# Overdrive.net
KiCad netlist of a schematic drawn in EAGLE
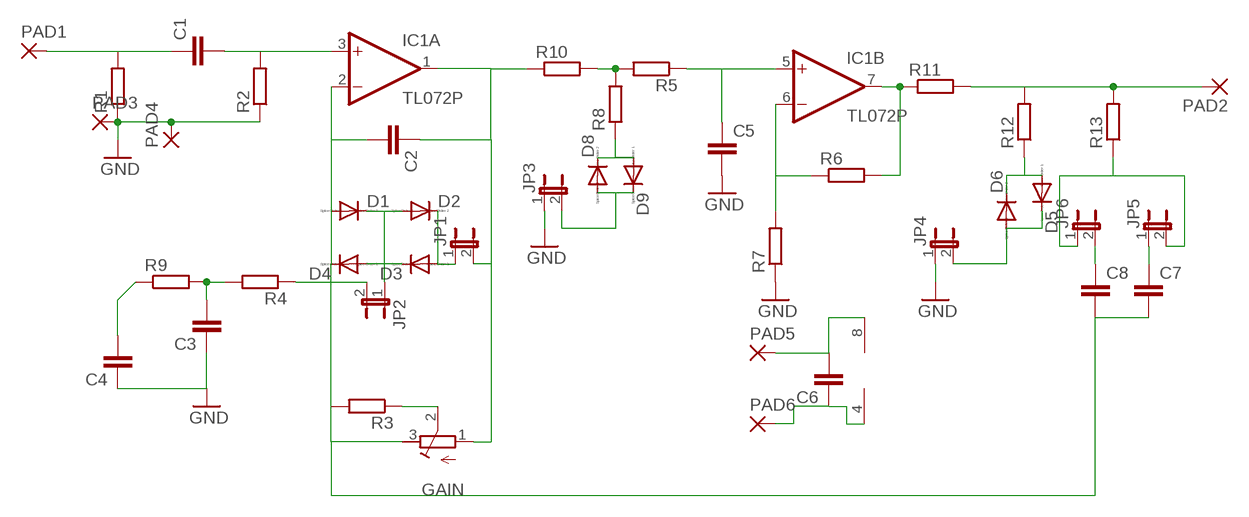
[diagram p0: schematic, sheet 1]

(export (version "E")
  (design (tool "Eeschema 10.0.6"))
  (components
    (comp (ref "C1")
      (value "C-EU050-030X075")
      (footprint "eagle-import:C050-030X075")
      (libsource (lib "eagle-import") (part "C-EU050-030X075"))
    )
    (comp (ref "C2")
      (value "C-EU050-030X075")
      (footprint "eagle-import:C050-030X075")
      (libsource (lib "eagle-import") (part "C-EU050-030X075"))
    )
    (comp (ref "C3")
      (value "C-EU050-030X075")
      (footprint "eagle-import:C050-030X075")
      (libsource (lib "eagle-import") (part "C-EU050-030X075"))
    )
    (comp (ref "C4")
      (value "C-EU050-030X075")
      (footprint "eagle-import:C050-030X075")
      (libsource (lib "eagle-import") (part "C-EU050-030X075"))
    )
    (comp (ref "C5")
      (value "C-EU050-030X075")
      (footprint "eagle-import:C050-030X075")
      (libsource (lib "eagle-import") (part "C-EU050-030X075"))
    )
    (comp (ref "C6")
      (value "C-EU050-030X075")
      (footprint "eagle-import:C050-030X075")
      (libsource (lib "eagle-import") (part "C-EU050-030X075"))
    )
    (comp (ref "C7")
      (value "C-EU050-030X075")
      (footprint "eagle-import:C050-030X075")
      (libsource (lib "eagle-import") (part "C-EU050-030X075"))
    )
    (comp (ref "C8")
      (value "C-EU050-030X075")
      (footprint "eagle-import:C050-030X075")
      (libsource (lib "eagle-import") (part "C-EU050-030X075"))
    )
    (comp (ref "D1")
      (value "1N4148DO35-7")
      (footprint "eagle-import:DO35-7")
      (libsource (lib "eagle-import") (part "1N4148DO35-7"))
    )
    (comp (ref "D2")
      (value "1N4148DO35-7")
      (footprint "eagle-import:DO35-7")
      (libsource (lib "eagle-import") (part "1N4148DO35-7"))
    )
    (comp (ref "D3")
      (value "1N4148DO35-7")
      (footprint "eagle-import:DO35-7")
      (libsource (lib "eagle-import") (part "1N4148DO35-7"))
    )
    (comp (ref "D4")
      (value "1N4148DO35-7")
      (footprint "eagle-import:DO35-7")
      (libsource (lib "eagle-import") (part "1N4148DO35-7"))
    )
    (comp (ref "D5")
      (value "1N4148DO35-7")
      (footprint "eagle-import:DO35-7")
      (libsource (lib "eagle-import") (part "1N4148DO35-7"))
    )
    (comp (ref "D6")
      (value "1N4148DO35-7")
      (footprint "eagle-import:DO35-7")
      (libsource (lib "eagle-import") (part "1N4148DO35-7"))
    )
    (comp (ref "D8")
      (value "1N4148DO35-7")
      (footprint "eagle-import:DO35-7")
      (libsource (lib "eagle-import") (part "1N4148DO35-7"))
    )
    (comp (ref "D9")
      (value "1N4148DO35-7")
      (footprint "eagle-import:DO35-7")
      (libsource (lib "eagle-import") (part "1N4148DO35-7"))
    )
    (comp (ref "GAIN")
      (value "R-TRIMM64W")
      (footprint "eagle-import:RTRIM64W")
      (libsource (lib "eagle-import") (part "R-TRIMM64W"))
    )
    (comp (ref "IC1")
      (value "TL072P")
      (footprint "eagle-import:DIL08")
      (libsource (lib "eagle-import") (part "TL072P"))
    )
    (comp (ref "JP1")
      (value "JP1E")
      (footprint "eagle-import:JP1")
      (libsource (lib "eagle-import") (part "JP1E"))
    )
    (comp (ref "JP2")
      (value "JP1E")
      (footprint "eagle-import:JP1")
      (libsource (lib "eagle-import") (part "JP1E"))
    )
    (comp (ref "JP3")
      (value "JP1E")
      (footprint "eagle-import:JP1")
      (libsource (lib "eagle-import") (part "JP1E"))
    )
    (comp (ref "JP4")
      (value "JP1E")
      (footprint "eagle-import:JP1")
      (libsource (lib "eagle-import") (part "JP1E"))
    )
    (comp (ref "JP5")
      (value "JP1E")
      (footprint "eagle-import:JP1")
      (libsource (lib "eagle-import") (part "JP1E"))
    )
    (comp (ref "JP6")
      (value "JP1E")
      (footprint "eagle-import:JP1")
      (libsource (lib "eagle-import") (part "JP1E"))
    )
    (comp (ref "PAD1")
      (value "WIREPAD2,54/0,8")
      (footprint "eagle-import:2,54_0,8")
      (libsource (lib "eagle-import") (part "WIREPAD2,54/0,8"))
    )
    (comp (ref "PAD2")
      (value "WIREPAD2,54/0,8")
      (footprint "eagle-import:2,54_0,8")
      (libsource (lib "eagle-import") (part "WIREPAD2,54/0,8"))
    )
    (comp (ref "PAD3")
      (value "WIREPAD2,54/0,8")
      (footprint "eagle-import:2,54_0,8")
      (libsource (lib "eagle-import") (part "WIREPAD2,54/0,8"))
    )
    (comp (ref "PAD4")
      (value "WIREPAD2,54/0,8")
      (footprint "eagle-import:2,54_0,8")
      (libsource (lib "eagle-import") (part "WIREPAD2,54/0,8"))
    )
    (comp (ref "PAD5")
      (value "WIREPAD2,54/0,8")
      (footprint "eagle-import:2,54_0,8")
      (libsource (lib "eagle-import") (part "WIREPAD2,54/0,8"))
    )
    (comp (ref "PAD6")
      (value "WIREPAD2,54/0,8")
      (footprint "eagle-import:2,54_0,8")
      (libsource (lib "eagle-import") (part "WIREPAD2,54/0,8"))
    )
    (comp (ref "R1")
      (value "R-EU_0207/7")
      (footprint "eagle-import:0207_7")
      (libsource (lib "eagle-import") (part "R-EU_0207/7"))
    )
    (comp (ref "R2")
      (value "R-EU_0207/7")
      (footprint "eagle-import:0207_7")
      (libsource (lib "eagle-import") (part "R-EU_0207/7"))
    )
    (comp (ref "R3")
      (value "R-EU_0207/7")
      (footprint "eagle-import:0207_7")
      (libsource (lib "eagle-import") (part "R-EU_0207/7"))
    )
    (comp (ref "R4")
      (value "R-EU_0207/7")
      (footprint "eagle-import:0207_7")
      (libsource (lib "eagle-import") (part "R-EU_0207/7"))
    )
    (comp (ref "R5")
      (value "R-EU_0207/7")
      (footprint "eagle-import:0207_7")
      (libsource (lib "eagle-import") (part "R-EU_0207/7"))
    )
    (comp (ref "R6")
      (value "R-EU_0207/7")
      (footprint "eagle-import:0207_7")
      (libsource (lib "eagle-import") (part "R-EU_0207/7"))
    )
    (comp (ref "R7")
      (value "R-EU_0207/7")
      (footprint "eagle-import:0207_7")
      (libsource (lib "eagle-import") (part "R-EU_0207/7"))
    )
    (comp (ref "R8")
      (value "R-EU_0207/7")
      (footprint "eagle-import:0207_7")
      (libsource (lib "eagle-import") (part "R-EU_0207/7"))
    )
    (comp (ref "R9")
      (value "R-EU_0207/7")
      (footprint "eagle-import:0207_7")
      (libsource (lib "eagle-import") (part "R-EU_0207/7"))
    )
    (comp (ref "R10")
      (value "R-EU_0207/7")
      (footprint "eagle-import:0207_7")
      (libsource (lib "eagle-import") (part "R-EU_0207/7"))
    )
    (comp (ref "R11")
      (value "R-EU_0207/7")
      (footprint "eagle-import:0207_7")
      (libsource (lib "eagle-import") (part "R-EU_0207/7"))
    )
    (comp (ref "R12")
      (value "R-EU_0207/7")
      (footprint "eagle-import:0207_7")
      (libsource (lib "eagle-import") (part "R-EU_0207/7"))
    )
    (comp (ref "R13")
      (value "R-EU_0207/7")
      (footprint "eagle-import:0207_7")
      (libsource (lib "eagle-import") (part "R-EU_0207/7"))
    )
  )
  (nets
    (net (code "1") (name "GND") (class "Default")
      (node (ref "C3") (pin "1") (pinfunction "1_1") (pintype "passive"))
      (node (ref "C4") (pin "1") (pinfunction "1_1") (pintype "passive"))
      (node (ref "C5") (pin "2") (pinfunction "2_2") (pintype "passive"))
      (node (ref "JP3") (pin "1") (pinfunction "1_1") (pintype "passive"))
      (node (ref "JP4") (pin "1") (pinfunction "1_1") (pintype "passive"))
      (node (ref "PAD3") (pin "1") (pinfunction "P_1") (pintype "passive"))
      (node (ref "PAD4") (pin "1") (pinfunction "P_1") (pintype "passive"))
      (node (ref "R1") (pin "1") (pinfunction "1_1") (pintype "passive"))
      (node (ref "R2") (pin "1") (pinfunction "1_1") (pintype "passive"))
      (node (ref "R7") (pin "1") (pinfunction "1_1") (pintype "passive"))
    )
    (net (code "2") (name "Net-(C3-Pad2)") (class "Default")
      (node (ref "C3") (pin "2") (pinfunction "2_2") (pintype "passive"))
      (node (ref "R4") (pin "2") (pinfunction "2_2") (pintype "passive"))
      (node (ref "R9") (pin "2") (pinfunction "2_2") (pintype "passive"))
    )
    (net (code "3") (name "Net-(C4-Pad2)") (class "Default")
      (node (ref "C4") (pin "2") (pinfunction "2_2") (pintype "passive"))
      (node (ref "R9") (pin "1") (pinfunction "1_1") (pintype "passive"))
    )
    (net (code "4") (name "Net-(C7-Pad1)") (class "Default")
      (node (ref "C7") (pin "1") (pinfunction "1_1") (pintype "passive"))
      (node (ref "JP5") (pin "1") (pinfunction "1_1") (pintype "passive"))
    )
    (net (code "5") (name "Net-(C8-Pad1)") (class "Default")
      (node (ref "C8") (pin "1") (pinfunction "1_1") (pintype "passive"))
      (node (ref "JP6") (pin "2") (pinfunction "2_2") (pintype "passive"))
    )
    (net (code "6") (name "Net-(D1-PadC)") (class "Default")
      (node (ref "D1") (pin "C") (pinfunction "C_C") (pintype "passive"))
      (node (ref "D2") (pin "A") (pinfunction "A_A") (pintype "passive"))
      (node (ref "D3") (pin "C") (pinfunction "C_C") (pintype "passive"))
      (node (ref "D4") (pin "A") (pinfunction "A_A") (pintype "passive"))
      (node (ref "JP2") (pin "1") (pinfunction "1_1") (pintype "passive"))
    )
    (net (code "7") (name "Net-(D2-PadC)") (class "Default")
      (node (ref "D2") (pin "C") (pinfunction "C_C") (pintype "passive"))
      (node (ref "D3") (pin "A") (pinfunction "A_A") (pintype "passive"))
      (node (ref "JP1") (pin "1") (pinfunction "1_1") (pintype "passive"))
    )
    (net (code "8") (name "Net-(D5-PadA)") (class "Default")
      (node (ref "D5") (pin "A") (pinfunction "A_A") (pintype "passive"))
      (node (ref "D6") (pin "C") (pinfunction "C_C") (pintype "passive"))
      (node (ref "R12") (pin "1") (pinfunction "1_1") (pintype "passive"))
    )
    (net (code "9") (name "Net-(D5-PadC)") (class "Default")
      (node (ref "D5") (pin "C") (pinfunction "C_C") (pintype "passive"))
      (node (ref "D6") (pin "A") (pinfunction "A_A") (pintype "passive"))
      (node (ref "JP4") (pin "2") (pinfunction "2_2") (pintype "passive"))
    )
    (net (code "10") (name "Net-(D8-PadA)") (class "Default")
      (node (ref "D8") (pin "A") (pinfunction "A_A") (pintype "passive"))
      (node (ref "D9") (pin "C") (pinfunction "C_C") (pintype "passive"))
      (node (ref "JP3") (pin "2") (pinfunction "2_2") (pintype "passive"))
    )
    (net (code "11") (name "Net-(D8-PadC)") (class "Default")
      (node (ref "D8") (pin "C") (pinfunction "C_C") (pintype "passive"))
      (node (ref "D9") (pin "A") (pinfunction "A_A") (pintype "passive"))
      (node (ref "R8") (pin "1") (pinfunction "1_1") (pintype "passive"))
    )
    (net (code "12") (name "Net-(GAIN-A)") (class "Default")
      (node (ref "C2") (pin "1") (pinfunction "1_1") (pintype "passive"))
      (node (ref "GAIN") (pin "1") (pinfunction "A_1") (pintype "passive"))
      (node (ref "IC1") (pin "1") (pinfunction "OUT_1") (pintype "output"))
      (node (ref "JP1") (pin "2") (pinfunction "2_2") (pintype "passive"))
      (node (ref "R10") (pin "1") (pinfunction "1_1") (pintype "passive"))
    )
    (net (code "13") (name "Net-(GAIN-E)") (class "Default")
      (node (ref "C2") (pin "2") (pinfunction "2_2") (pintype "passive"))
      (node (ref "C7") (pin "2") (pinfunction "2_2") (pintype "passive"))
      (node (ref "C8") (pin "2") (pinfunction "2_2") (pintype "passive"))
      (node (ref "D1") (pin "A") (pinfunction "A_A") (pintype "passive"))
      (node (ref "D4") (pin "C") (pinfunction "C_C") (pintype "passive"))
      (node (ref "GAIN") (pin "3") (pinfunction "E_3") (pintype "passive"))
      (node (ref "IC1") (pin "2") (pinfunction "-IN_2") (pintype "input"))
      (node (ref "JP2") (pin "2") (pinfunction "2_2") (pintype "passive"))
      (node (ref "R3") (pin "2") (pinfunction "2_2") (pintype "passive"))
      (node (ref "R4") (pin "1") (pinfunction "1_1") (pintype "passive"))
    )
    (net (code "14") (name "Net-(GAIN-S)") (class "Default")
      (node (ref "GAIN") (pin "2") (pinfunction "S_2") (pintype "passive"))
      (node (ref "R3") (pin "1") (pinfunction "1_1") (pintype "passive"))
    )
    (net (code "15") (name "Net-(IC1A-+IN)") (class "Default")
      (node (ref "C1") (pin "2") (pinfunction "2_2") (pintype "passive"))
      (node (ref "IC1") (pin "3") (pinfunction "+IN_3") (pintype "input"))
      (node (ref "R2") (pin "2") (pinfunction "2_2") (pintype "passive"))
    )
    (net (code "16") (name "Net-(IC1B-+IN)") (class "Default")
      (node (ref "C5") (pin "1") (pinfunction "1_1") (pintype "passive"))
      (node (ref "IC1") (pin "5") (pinfunction "+IN_5") (pintype "input"))
      (node (ref "R5") (pin "1") (pinfunction "1_1") (pintype "passive"))
    )
    (net (code "17") (name "Net-(IC1B--IN)") (class "Default")
      (node (ref "IC1") (pin "6") (pinfunction "-IN_6") (pintype "input"))
      (node (ref "R6") (pin "1") (pinfunction "1_1") (pintype "passive"))
      (node (ref "R7") (pin "2") (pinfunction "2_2") (pintype "passive"))
    )
    (net (code "18") (name "Net-(IC1B-OUT)") (class "Default")
      (node (ref "IC1") (pin "7") (pinfunction "OUT_7") (pintype "output"))
      (node (ref "R11") (pin "1") (pinfunction "1_1") (pintype "passive"))
      (node (ref "R6") (pin "2") (pinfunction "2_2") (pintype "passive"))
    )
    (net (code "19") (name "Net-(IC1C-V+)") (class "Default")
      (node (ref "C6") (pin "2") (pinfunction "2_2") (pintype "passive"))
      (node (ref "IC1") (pin "8") (pinfunction "V+_8") (pintype "power_in"))
      (node (ref "PAD5") (pin "1") (pinfunction "P_1") (pintype "passive"))
    )
    (net (code "20") (name "Net-(IC1C-V-)") (class "Default")
      (node (ref "C6") (pin "1") (pinfunction "1_1") (pintype "passive"))
      (node (ref "IC1") (pin "4") (pinfunction "V-_4") (pintype "power_in"))
      (node (ref "PAD6") (pin "1") (pinfunction "P_1") (pintype "passive"))
    )
    (net (code "21") (name "Net-(JP5-Pad2)") (class "Default")
      (node (ref "JP5") (pin "2") (pinfunction "2_2") (pintype "passive"))
      (node (ref "JP6") (pin "1") (pinfunction "1_1") (pintype "passive"))
      (node (ref "R13") (pin "1") (pinfunction "1_1") (pintype "passive"))
    )
    (net (code "22") (name "Net-(PAD1-P)") (class "Default")
      (node (ref "C1") (pin "1") (pinfunction "1_1") (pintype "passive"))
      (node (ref "PAD1") (pin "1") (pinfunction "P_1") (pintype "passive"))
      (node (ref "R1") (pin "2") (pinfunction "2_2") (pintype "passive"))
    )
    (net (code "23") (name "Net-(PAD2-P)") (class "Default")
      (node (ref "PAD2") (pin "1") (pinfunction "P_1") (pintype "passive"))
      (node (ref "R11") (pin "2") (pinfunction "2_2") (pintype "passive"))
      (node (ref "R12") (pin "2") (pinfunction "2_2") (pintype "passive"))
      (node (ref "R13") (pin "2") (pinfunction "2_2") (pintype "passive"))
    )
    (net (code "24") (name "Net-(R10-Pad2)") (class "Default")
      (node (ref "R10") (pin "2") (pinfunction "2_2") (pintype "passive"))
      (node (ref "R5") (pin "2") (pinfunction "2_2") (pintype "passive"))
      (node (ref "R8") (pin "2") (pinfunction "2_2") (pintype "passive"))
    )
  )
)
